# B212C.net
KiCad netlist of a schematic drawn in EAGLE
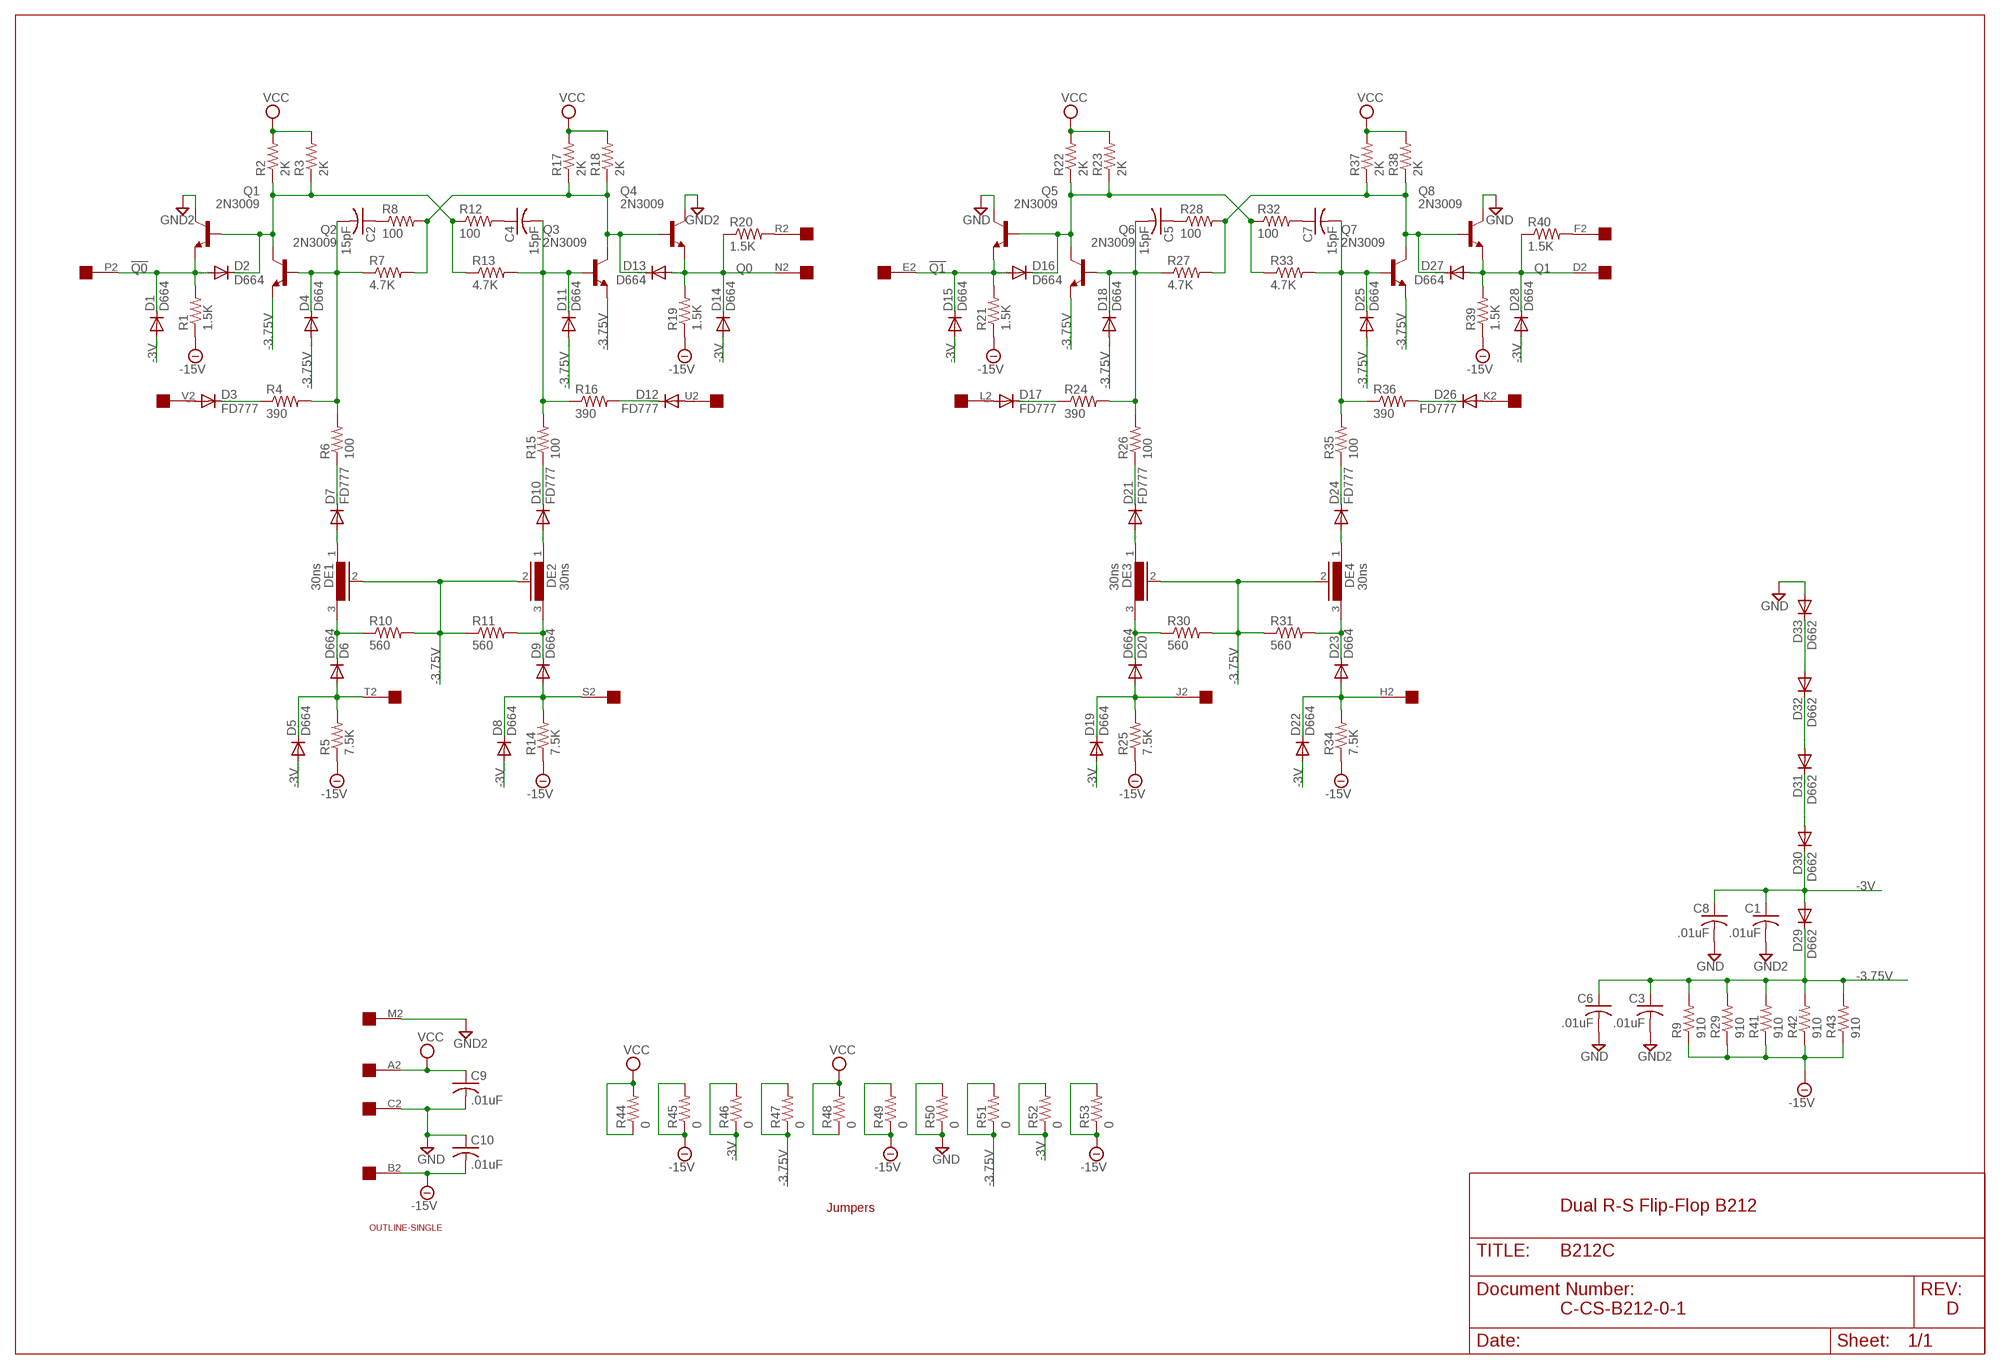
[diagram p0: schematic, sheet 1]

(export (version "E")
  (design (tool "Eeschema 10.0.6"))
  (components
    (comp (ref "C1")
      (value ".01uF")
      (footprint "eagle-import:C063-025X075")
      (libsource (lib "eagle-import") (part "C-US"))
    )
    (comp (ref "C2")
      (value "15pF")
      (footprint "eagle-import:C063-025X075")
      (libsource (lib "eagle-import") (part "C-US"))
    )
    (comp (ref "C3")
      (value ".01uF")
      (footprint "eagle-import:C063-025X075")
      (libsource (lib "eagle-import") (part "C-US"))
    )
    (comp (ref "C4")
      (value "15pF")
      (footprint "eagle-import:C050-025X075")
      (libsource (lib "eagle-import") (part "C-US050-025X075"))
    )
    (comp (ref "C5")
      (value "15pF")
      (footprint "eagle-import:C063-025X075")
      (libsource (lib "eagle-import") (part "C-US"))
    )
    (comp (ref "C6")
      (value ".01uF")
      (footprint "eagle-import:C063-025X075")
      (libsource (lib "eagle-import") (part "C-US"))
    )
    (comp (ref "C7")
      (value "15pF")
      (footprint "eagle-import:C063-025X075")
      (libsource (lib "eagle-import") (part "C-US"))
    )
    (comp (ref "C8")
      (value ".01uF")
      (footprint "eagle-import:C063-025X075")
      (libsource (lib "eagle-import") (part "C-US"))
    )
    (comp (ref "C9")
      (value ".01uF")
      (footprint "eagle-import:C063-025X075")
      (libsource (lib "eagle-import") (part "C-US"))
    )
    (comp (ref "C10")
      (value ".01uF")
      (footprint "eagle-import:C063-025X075")
      (libsource (lib "eagle-import") (part "C-US"))
    )
    (comp (ref "D1")
      (value "D664")
      (footprint "eagle-import:DO35-10")
      (libsource (lib "eagle-import") (part "DIODE-DO35-10"))
    )
    (comp (ref "D2")
      (value "D664")
      (footprint "eagle-import:DO35-10")
      (libsource (lib "eagle-import") (part "DIODE-DO35-10"))
    )
    (comp (ref "D3")
      (value "FD777")
      (footprint "eagle-import:DO35-10")
      (libsource (lib "eagle-import") (part "DIODE-DO35-10"))
    )
    (comp (ref "D4")
      (value "D664")
      (footprint "eagle-import:DO35-10")
      (libsource (lib "eagle-import") (part "DIODE-DO35-10"))
    )
    (comp (ref "D5")
      (value "D664")
      (footprint "eagle-import:DO35-10")
      (libsource (lib "eagle-import") (part "DIODE-DO35-10"))
    )
    (comp (ref "D6")
      (value "D664")
      (footprint "eagle-import:DO35-10")
      (libsource (lib "eagle-import") (part "DIODE-DO35-10"))
    )
    (comp (ref "D7")
      (value "FD777")
      (footprint "eagle-import:DO35-10")
      (libsource (lib "eagle-import") (part "DIODE-DO35-10"))
    )
    (comp (ref "D8")
      (value "D664")
      (footprint "eagle-import:DO35-10")
      (libsource (lib "eagle-import") (part "DIODE-DO35-10"))
    )
    (comp (ref "D9")
      (value "D664")
      (footprint "eagle-import:DO35-10")
      (libsource (lib "eagle-import") (part "DIODE-DO35-10"))
    )
    (comp (ref "D10")
      (value "FD777")
      (footprint "eagle-import:DO35-10")
      (libsource (lib "eagle-import") (part "DIODE-DO35-10"))
    )
    (comp (ref "D11")
      (value "D664")
      (footprint "eagle-import:DO35-10")
      (libsource (lib "eagle-import") (part "DIODE-DO35-10"))
    )
    (comp (ref "D12")
      (value "FD777")
      (footprint "eagle-import:DO35-10")
      (libsource (lib "eagle-import") (part "DIODE-DO35-10"))
    )
    (comp (ref "D13")
      (value "D664")
      (footprint "eagle-import:DO35-10")
      (libsource (lib "eagle-import") (part "DIODE-DO35-10"))
    )
    (comp (ref "D14")
      (value "D664")
      (footprint "eagle-import:DO35-10")
      (libsource (lib "eagle-import") (part "DIODE-DO35-10"))
    )
    (comp (ref "D15")
      (value "D664")
      (footprint "eagle-import:DO35-10")
      (libsource (lib "eagle-import") (part "DIODE-DO35-10"))
    )
    (comp (ref "D16")
      (value "D664")
      (footprint "eagle-import:DO35-10")
      (libsource (lib "eagle-import") (part "DIODE-DO35-10"))
    )
    (comp (ref "D17")
      (value "FD777")
      (footprint "eagle-import:DO35-10")
      (libsource (lib "eagle-import") (part "DIODE-DO35-10"))
    )
    (comp (ref "D18")
      (value "D664")
      (footprint "eagle-import:DO35-10")
      (libsource (lib "eagle-import") (part "DIODE-DO35-10"))
    )
    (comp (ref "D19")
      (value "D664")
      (footprint "eagle-import:DO35-10")
      (libsource (lib "eagle-import") (part "DIODE-DO35-10"))
    )
    (comp (ref "D20")
      (value "D664")
      (footprint "eagle-import:DO35-10")
      (libsource (lib "eagle-import") (part "DIODE-DO35-10"))
    )
    (comp (ref "D21")
      (value "FD777")
      (footprint "eagle-import:DO35-10")
      (libsource (lib "eagle-import") (part "DIODE-DO35-10"))
    )
    (comp (ref "D22")
      (value "D664")
      (footprint "eagle-import:DO35-10")
      (libsource (lib "eagle-import") (part "DIODE-DO35-10"))
    )
    (comp (ref "D23")
      (value "D664")
      (footprint "eagle-import:DO35-10")
      (libsource (lib "eagle-import") (part "DIODE-DO35-10"))
    )
    (comp (ref "D24")
      (value "FD777")
      (footprint "eagle-import:DO35-10")
      (libsource (lib "eagle-import") (part "DIODE-DO35-10"))
    )
    (comp (ref "D25")
      (value "D664")
      (footprint "eagle-import:DO35-10")
      (libsource (lib "eagle-import") (part "DIODE-DO35-10"))
    )
    (comp (ref "D26")
      (value "FD777")
      (footprint "eagle-import:DO35-10")
      (libsource (lib "eagle-import") (part "DIODE-DO35-10"))
    )
    (comp (ref "D27")
      (value "D664")
      (footprint "eagle-import:DO35-10")
      (libsource (lib "eagle-import") (part "DIODE-DO35-10"))
    )
    (comp (ref "D28")
      (value "D664")
      (footprint "eagle-import:DO35-10")
      (libsource (lib "eagle-import") (part "DIODE-DO35-10"))
    )
    (comp (ref "D29")
      (value "D662")
      (footprint "eagle-import:DO35-10")
      (libsource (lib "eagle-import") (part "DIODE-DO35-10"))
    )
    (comp (ref "D30")
      (value "D662")
      (footprint "eagle-import:DO35-10")
      (libsource (lib "eagle-import") (part "DIODE-DO35-10"))
    )
    (comp (ref "D31")
      (value "D662")
      (footprint "eagle-import:DO35-10")
      (libsource (lib "eagle-import") (part "DIODE-DO35-10"))
    )
    (comp (ref "D32")
      (value "D662")
      (footprint "eagle-import:DO35-10")
      (libsource (lib "eagle-import") (part "DIODE-DO35-10"))
    )
    (comp (ref "D33")
      (value "D662")
      (footprint "eagle-import:DO35-10")
      (libsource (lib "eagle-import") (part "DIODE-DO35-10"))
    )
    (comp (ref "DE1")
      (value "30ns")
      (footprint "eagle-import:RCL-L-00-05")
      (libsource (lib "eagle-import") (part "RCL-L-00-05"))
    )
    (comp (ref "DE2")
      (value "30ns")
      (footprint "eagle-import:RCL-L-00-05")
      (libsource (lib "eagle-import") (part "RCL-L-00-05"))
    )
    (comp (ref "DE3")
      (value "30ns")
      (footprint "eagle-import:RCL-L-00-05")
      (libsource (lib "eagle-import") (part "RCL-L-00-05"))
    )
    (comp (ref "DE4")
      (value "30ns")
      (footprint "eagle-import:RCL-L-00-05")
      (libsource (lib "eagle-import") (part "RCL-L-00-05"))
    )
    (comp (ref "Q1")
      (value "2N3009")
      (footprint "eagle-import:TO5")
      (libsource (lib "eagle-import") (part "-NPN-TO5"))
    )
    (comp (ref "Q2")
      (value "2N3009")
      (footprint "eagle-import:TO5")
      (libsource (lib "eagle-import") (part "-NPN-TO5"))
    )
    (comp (ref "Q3")
      (value "2N3009")
      (footprint "eagle-import:TO5")
      (libsource (lib "eagle-import") (part "-NPN-TO5"))
    )
    (comp (ref "Q4")
      (value "2N3009")
      (footprint "eagle-import:TO5")
      (libsource (lib "eagle-import") (part "-NPN-TO5"))
    )
    (comp (ref "Q5")
      (value "2N3009")
      (footprint "eagle-import:TO5")
      (libsource (lib "eagle-import") (part "-NPN-TO5"))
    )
    (comp (ref "Q6")
      (value "2N3009")
      (footprint "eagle-import:TO5")
      (libsource (lib "eagle-import") (part "-NPN-TO5"))
    )
    (comp (ref "Q7")
      (value "2N3009")
      (footprint "eagle-import:TO5")
      (libsource (lib "eagle-import") (part "-NPN-TO5"))
    )
    (comp (ref "Q8")
      (value "2N3009")
      (footprint "eagle-import:TO5")
      (libsource (lib "eagle-import") (part "-NPN-TO5"))
    )
    (comp (ref "R1")
      (value "1.5K")
      (footprint "eagle-import:0207_10")
      (libsource (lib "eagle-import") (part "R-US_0207/10"))
    )
    (comp (ref "R2")
      (value "2K")
      (footprint "eagle-import:0207_10")
      (libsource (lib "eagle-import") (part "R-US_0207/10"))
    )
    (comp (ref "R3")
      (value "2K")
      (footprint "eagle-import:0207_10")
      (libsource (lib "eagle-import") (part "R-US_0207/10"))
    )
    (comp (ref "R4")
      (value "390")
      (footprint "eagle-import:0207_10")
      (libsource (lib "eagle-import") (part "R-US_0207/10"))
    )
    (comp (ref "R5")
      (value "7.5K")
      (footprint "eagle-import:0207_10")
      (libsource (lib "eagle-import") (part "R-US_0207/10"))
    )
    (comp (ref "R6")
      (value "100")
      (footprint "eagle-import:0207_10")
      (libsource (lib "eagle-import") (part "R-US_0207/10"))
    )
    (comp (ref "R7")
      (value "4.7K")
      (footprint "eagle-import:0207_10")
      (libsource (lib "eagle-import") (part "R-US_0207/10"))
    )
    (comp (ref "R8")
      (value "100")
      (footprint "eagle-import:0207_10")
      (libsource (lib "eagle-import") (part "R-US_0207/10"))
    )
    (comp (ref "R9")
      (value "910")
      (footprint "eagle-import:0207_10")
      (libsource (lib "eagle-import") (part "R-US_0207/10"))
    )
    (comp (ref "R10")
      (value "560")
      (footprint "eagle-import:0207_10")
      (libsource (lib "eagle-import") (part "R-US_0207/10"))
    )
    (comp (ref "R11")
      (value "560")
      (footprint "eagle-import:0207_10")
      (libsource (lib "eagle-import") (part "R-US_0207/10"))
    )
    (comp (ref "R12")
      (value "100")
      (footprint "eagle-import:0207_10")
      (libsource (lib "eagle-import") (part "R-US_0207/10"))
    )
    (comp (ref "R13")
      (value "4.7K")
      (footprint "eagle-import:0207_10")
      (libsource (lib "eagle-import") (part "R-US_0207/10"))
    )
    (comp (ref "R14")
      (value "7.5K")
      (footprint "eagle-import:0207_10")
      (libsource (lib "eagle-import") (part "R-US_0207/10"))
    )
    (comp (ref "R15")
      (value "100")
      (footprint "eagle-import:0207_10")
      (libsource (lib "eagle-import") (part "R-US_0207/10"))
    )
    (comp (ref "R16")
      (value "390")
      (footprint "eagle-import:0207_10")
      (libsource (lib "eagle-import") (part "R-US_0207/10"))
    )
    (comp (ref "R17")
      (value "2K")
      (footprint "eagle-import:0207_10")
      (libsource (lib "eagle-import") (part "R-US_0207/10"))
    )
    (comp (ref "R18")
      (value "2K")
      (footprint "eagle-import:0207_10")
      (libsource (lib "eagle-import") (part "R-US_0207/10"))
    )
    (comp (ref "R19")
      (value "1.5K")
      (footprint "eagle-import:0207_10")
      (libsource (lib "eagle-import") (part "R-US_0207/10"))
    )
    (comp (ref "R20")
      (value "1.5K")
      (footprint "eagle-import:0207_10")
      (libsource (lib "eagle-import") (part "R-US_0207/10"))
    )
    (comp (ref "R21")
      (value "1.5K")
      (footprint "eagle-import:0207_10")
      (libsource (lib "eagle-import") (part "R-US_0207/10"))
    )
    (comp (ref "R22")
      (value "2K")
      (footprint "eagle-import:0207_10")
      (libsource (lib "eagle-import") (part "R-US_0207/10"))
    )
    (comp (ref "R23")
      (value "2K")
      (footprint "eagle-import:0207_10")
      (libsource (lib "eagle-import") (part "R-US_0207/10"))
    )
    (comp (ref "R24")
      (value "390")
      (footprint "eagle-import:0207_10")
      (libsource (lib "eagle-import") (part "R-US_0207/10"))
    )
    (comp (ref "R25")
      (value "7.5K")
      (footprint "eagle-import:0207_10")
      (libsource (lib "eagle-import") (part "R-US_0207/10"))
    )
    (comp (ref "R26")
      (value "100")
      (footprint "eagle-import:0207_10")
      (libsource (lib "eagle-import") (part "R-US_0207/10"))
    )
    (comp (ref "R27")
      (value "4.7K")
      (footprint "eagle-import:0207_10")
      (libsource (lib "eagle-import") (part "R-US_0207/10"))
    )
    (comp (ref "R28")
      (value "100")
      (footprint "eagle-import:0207_10")
      (libsource (lib "eagle-import") (part "R-US_0207/10"))
    )
    (comp (ref "R29")
      (value "910")
      (footprint "eagle-import:0207_10")
      (libsource (lib "eagle-import") (part "R-US_0207/10"))
    )
    (comp (ref "R30")
      (value "560")
      (footprint "eagle-import:0207_10")
      (libsource (lib "eagle-import") (part "R-US_0207/10"))
    )
    (comp (ref "R31")
      (value "560")
      (footprint "eagle-import:0207_10")
      (libsource (lib "eagle-import") (part "R-US_0207/10"))
    )
    (comp (ref "R32")
      (value "100")
      (footprint "eagle-import:0207_10")
      (libsource (lib "eagle-import") (part "R-US_0207/10"))
    )
    (comp (ref "R33")
      (value "4.7K")
      (footprint "eagle-import:0207_10")
      (libsource (lib "eagle-import") (part "R-US_0207/10"))
    )
    (comp (ref "R34")
      (value "7.5K")
      (footprint "eagle-import:0207_10")
      (libsource (lib "eagle-import") (part "R-US_0207/10"))
    )
    (comp (ref "R35")
      (value "100")
      (footprint "eagle-import:0207_10")
      (libsource (lib "eagle-import") (part "R-US_0207/10"))
    )
    (comp (ref "R36")
      (value "390")
      (footprint "eagle-import:0207_10")
      (libsource (lib "eagle-import") (part "R-US_0207/10"))
    )
    (comp (ref "R37")
      (value "2K")
      (footprint "eagle-import:0207_10")
      (libsource (lib "eagle-import") (part "R-US_0207/10"))
    )
    (comp (ref "R38")
      (value "2K")
      (footprint "eagle-import:0207_10")
      (libsource (lib "eagle-import") (part "R-US_0207/10"))
    )
    (comp (ref "R39")
      (value "1.5K")
      (footprint "eagle-import:0207_10")
      (libsource (lib "eagle-import") (part "R-US_0207/10"))
    )
    (comp (ref "R40")
      (value "1.5K")
      (footprint "eagle-import:0207_10")
      (libsource (lib "eagle-import") (part "R-US_0207/10"))
    )
    (comp (ref "R41")
      (value "910")
      (footprint "eagle-import:0207_10")
      (libsource (lib "eagle-import") (part "R-US_0207/10"))
    )
    (comp (ref "R42")
      (value "910")
      (footprint "eagle-import:0207_10")
      (libsource (lib "eagle-import") (part "R-US_0207/10"))
    )
    (comp (ref "R43")
      (value "910")
      (footprint "eagle-import:0207_10")
      (libsource (lib "eagle-import") (part "R-US_0207/10"))
    )
    (comp (ref "R44")
      (value "0")
      (footprint "eagle-import:0207_10")
      (libsource (lib "eagle-import") (part "R-US_0207/10"))
    )
    (comp (ref "R45")
      (value "0")
      (footprint "eagle-import:0207_10")
      (libsource (lib "eagle-import") (part "R-US_0207/10"))
    )
    (comp (ref "R46")
      (value "0")
      (footprint "eagle-import:0207_10")
      (libsource (lib "eagle-import") (part "R-US_0207/10"))
    )
    (comp (ref "R47")
      (value "0")
      (footprint "eagle-import:0207_10")
      (libsource (lib "eagle-import") (part "R-US_0207/10"))
    )
    (comp (ref "R48")
      (value "0")
      (footprint "eagle-import:0207_10")
      (libsource (lib "eagle-import") (part "R-US_0207/10"))
    )
    (comp (ref "R49")
      (value "0")
      (footprint "eagle-import:0207_10")
      (libsource (lib "eagle-import") (part "R-US_0207/10"))
    )
    (comp (ref "R50")
      (value "0")
      (footprint "eagle-import:0207_10")
      (libsource (lib "eagle-import") (part "R-US_0207/10"))
    )
    (comp (ref "R51")
      (value "0")
      (footprint "eagle-import:0207_10")
      (libsource (lib "eagle-import") (part "R-US_0207/10"))
    )
    (comp (ref "R52")
      (value "0")
      (footprint "eagle-import:0207_10")
      (libsource (lib "eagle-import") (part "R-US_0207/10"))
    )
    (comp (ref "R53")
      (value "0")
      (footprint "eagle-import:0207_10")
      (libsource (lib "eagle-import") (part "R-US_0207/10"))
    )
    (comp (ref "U$1")
      (value "OUTLINE-SINGLE")
      (footprint "eagle-import:SINGLE")
      (libsource (lib "eagle-import") (part "OUTLINE-SINGLE"))
    )
    (comp (ref "U$2")
      (value "EDGE-1")
      (footprint "eagle-import:EDGE-CON1")
      (libsource (lib "eagle-import") (part "EDGE-1"))
    )
  )
  (nets
    (net (code "1") (name "-15V") (class "Default")
      (node (ref "C10") (pin "2") (pinfunction "2_2") (pintype "passive"))
      (node (ref "R1") (pin "1") (pinfunction "1_1") (pintype "passive"))
      (node (ref "R14") (pin "1") (pinfunction "1_1") (pintype "passive"))
      (node (ref "R19") (pin "1") (pinfunction "1_1") (pintype "passive"))
      (node (ref "R21") (pin "1") (pinfunction "1_1") (pintype "passive"))
      (node (ref "R25") (pin "1") (pinfunction "1_1") (pintype "passive"))
      (node (ref "R29") (pin "1") (pinfunction "1_1") (pintype "passive"))
      (node (ref "R34") (pin "1") (pinfunction "1_1") (pintype "passive"))
      (node (ref "R39") (pin "1") (pinfunction "1_1") (pintype "passive"))
      (node (ref "R41") (pin "1") (pinfunction "1_1") (pintype "passive"))
      (node (ref "R42") (pin "1") (pinfunction "1_1") (pintype "passive"))
      (node (ref "R43") (pin "1") (pinfunction "1_1") (pintype "passive"))
      (node (ref "R45") (pin "1") (pinfunction "1_1") (pintype "passive"))
      (node (ref "R45") (pin "2") (pinfunction "2_2") (pintype "passive"))
      (node (ref "R49") (pin "1") (pinfunction "1_1") (pintype "passive"))
      (node (ref "R49") (pin "2") (pinfunction "2_2") (pintype "passive"))
      (node (ref "R5") (pin "1") (pinfunction "1_1") (pintype "passive"))
      (node (ref "R53") (pin "1") (pinfunction "1_1") (pintype "passive"))
      (node (ref "R53") (pin "2") (pinfunction "2_2") (pintype "passive"))
      (node (ref "R9") (pin "1") (pinfunction "1_1") (pintype "passive"))
      (node (ref "U$2") (pin "B2") (pinfunction "1_B2") (pintype "bidirectional"))
    )
    (net (code "2") (name "/-3.75V") (class "Default")
      (node (ref "C3") (pin "1") (pinfunction "1_1") (pintype "passive"))
      (node (ref "C6") (pin "1") (pinfunction "1_1") (pintype "passive"))
      (node (ref "D11") (pin "A") (pinfunction "A_A") (pintype "passive"))
      (node (ref "D18") (pin "A") (pinfunction "A_A") (pintype "passive"))
      (node (ref "D25") (pin "A") (pinfunction "A_A") (pintype "passive"))
      (node (ref "D29") (pin "C") (pinfunction "C_C") (pintype "passive"))
      (node (ref "D4") (pin "A") (pinfunction "A_A") (pintype "passive"))
      (node (ref "DE1") (pin "2") (pinfunction "2_2") (pintype "passive"))
      (node (ref "DE2") (pin "2") (pinfunction "2_2") (pintype "passive"))
      (node (ref "DE3") (pin "2") (pinfunction "2_2") (pintype "passive"))
      (node (ref "DE4") (pin "2") (pinfunction "2_2") (pintype "passive"))
      (node (ref "Q2") (pin "1") (pinfunction "E_1") (pintype "passive"))
      (node (ref "Q3") (pin "1") (pinfunction "E_1") (pintype "passive"))
      (node (ref "Q6") (pin "1") (pinfunction "E_1") (pintype "passive"))
      (node (ref "Q7") (pin "1") (pinfunction "E_1") (pintype "passive"))
      (node (ref "R10") (pin "2") (pinfunction "2_2") (pintype "passive"))
      (node (ref "R11") (pin "1") (pinfunction "1_1") (pintype "passive"))
      (node (ref "R29") (pin "2") (pinfunction "2_2") (pintype "passive"))
      (node (ref "R30") (pin "2") (pinfunction "2_2") (pintype "passive"))
      (node (ref "R31") (pin "1") (pinfunction "1_1") (pintype "passive"))
      (node (ref "R41") (pin "2") (pinfunction "2_2") (pintype "passive"))
      (node (ref "R42") (pin "2") (pinfunction "2_2") (pintype "passive"))
      (node (ref "R43") (pin "2") (pinfunction "2_2") (pintype "passive"))
      (node (ref "R47") (pin "1") (pinfunction "1_1") (pintype "passive"))
      (node (ref "R47") (pin "2") (pinfunction "2_2") (pintype "passive"))
      (node (ref "R51") (pin "1") (pinfunction "1_1") (pintype "passive"))
      (node (ref "R51") (pin "2") (pinfunction "2_2") (pintype "passive"))
      (node (ref "R9") (pin "2") (pinfunction "2_2") (pintype "passive"))
    )
    (net (code "3") (name "/-3V") (class "Default")
      (node (ref "C1") (pin "1") (pinfunction "1_1") (pintype "passive"))
      (node (ref "C8") (pin "1") (pinfunction "1_1") (pintype "passive"))
      (node (ref "D1") (pin "A") (pinfunction "A_A") (pintype "passive"))
      (node (ref "D14") (pin "A") (pinfunction "A_A") (pintype "passive"))
      (node (ref "D15") (pin "A") (pinfunction "A_A") (pintype "passive"))
      (node (ref "D19") (pin "A") (pinfunction "A_A") (pintype "passive"))
      (node (ref "D22") (pin "A") (pinfunction "A_A") (pintype "passive"))
      (node (ref "D28") (pin "A") (pinfunction "A_A") (pintype "passive"))
      (node (ref "D29") (pin "A") (pinfunction "A_A") (pintype "passive"))
      (node (ref "D30") (pin "C") (pinfunction "C_C") (pintype "passive"))
      (node (ref "D5") (pin "A") (pinfunction "A_A") (pintype "passive"))
      (node (ref "D8") (pin "A") (pinfunction "A_A") (pintype "passive"))
      (node (ref "R46") (pin "1") (pinfunction "1_1") (pintype "passive"))
      (node (ref "R46") (pin "2") (pinfunction "2_2") (pintype "passive"))
      (node (ref "R52") (pin "1") (pinfunction "1_1") (pintype "passive"))
      (node (ref "R52") (pin "2") (pinfunction "2_2") (pintype "passive"))
    )
    (net (code "4") (name "/Q0") (class "Default")
      (node (ref "D13") (pin "A") (pinfunction "A_A") (pintype "passive"))
      (node (ref "D14") (pin "C") (pinfunction "C_C") (pintype "passive"))
      (node (ref "Q4") (pin "1") (pinfunction "E_1") (pintype "passive"))
      (node (ref "R19") (pin "2") (pinfunction "2_2") (pintype "passive"))
      (node (ref "R20") (pin "1") (pinfunction "1_1") (pintype "passive"))
      (node (ref "U$2") (pin "N2") (pinfunction "1_N2") (pintype "bidirectional"))
    )
    (net (code "5") (name "/Q1") (class "Default")
      (node (ref "D27") (pin "A") (pinfunction "A_A") (pintype "passive"))
      (node (ref "D28") (pin "C") (pinfunction "C_C") (pintype "passive"))
      (node (ref "Q8") (pin "1") (pinfunction "E_1") (pintype "passive"))
      (node (ref "R39") (pin "2") (pinfunction "2_2") (pintype "passive"))
      (node (ref "R40") (pin "1") (pinfunction "1_1") (pintype "passive"))
      (node (ref "U$2") (pin "D2") (pinfunction "1_D2") (pintype "bidirectional"))
    )
    (net (code "6") (name "/~{Q0}") (class "Default")
      (node (ref "D1") (pin "C") (pinfunction "C_C") (pintype "passive"))
      (node (ref "D2") (pin "A") (pinfunction "A_A") (pintype "passive"))
      (node (ref "Q1") (pin "1") (pinfunction "E_1") (pintype "passive"))
      (node (ref "R1") (pin "2") (pinfunction "2_2") (pintype "passive"))
      (node (ref "U$2") (pin "P2") (pinfunction "1_P2") (pintype "bidirectional"))
    )
    (net (code "7") (name "/~{Q1}") (class "Default")
      (node (ref "D15") (pin "C") (pinfunction "C_C") (pintype "passive"))
      (node (ref "D16") (pin "A") (pinfunction "A_A") (pintype "passive"))
      (node (ref "Q5") (pin "1") (pinfunction "E_1") (pintype "passive"))
      (node (ref "R21") (pin "2") (pinfunction "2_2") (pintype "passive"))
      (node (ref "U$2") (pin "E2") (pinfunction "1_E2") (pintype "bidirectional"))
    )
    (net (code "8") (name "GND") (class "Default")
      (node (ref "C10") (pin "1") (pinfunction "1_1") (pintype "passive"))
      (node (ref "C6") (pin "2") (pinfunction "2_2") (pintype "passive"))
      (node (ref "C8") (pin "2") (pinfunction "2_2") (pintype "passive"))
      (node (ref "C9") (pin "2") (pinfunction "2_2") (pintype "passive"))
      (node (ref "D33") (pin "A") (pinfunction "A_A") (pintype "passive"))
      (node (ref "Q5") (pin "3") (pinfunction "C_3") (pintype "passive"))
      (node (ref "Q8") (pin "3") (pinfunction "C_3") (pintype "passive"))
      (node (ref "R50") (pin "1") (pinfunction "1_1") (pintype "passive"))
      (node (ref "R50") (pin "2") (pinfunction "2_2") (pintype "passive"))
      (node (ref "U$2") (pin "C2") (pinfunction "1_C2") (pintype "bidirectional"))
    )
    (net (code "9") (name "GND2") (class "Default")
      (node (ref "C1") (pin "2") (pinfunction "2_2") (pintype "passive"))
      (node (ref "C3") (pin "2") (pinfunction "2_2") (pintype "passive"))
      (node (ref "Q1") (pin "3") (pinfunction "C_3") (pintype "passive"))
      (node (ref "Q4") (pin "3") (pinfunction "C_3") (pintype "passive"))
      (node (ref "U$2") (pin "M2") (pinfunction "1_M2") (pintype "bidirectional"))
    )
    (net (code "10") (name "Net-(C2-Pad1)") (class "Default")
      (node (ref "C2") (pin "1") (pinfunction "1_1") (pintype "passive"))
      (node (ref "R8") (pin "1") (pinfunction "1_1") (pintype "passive"))
    )
    (net (code "11") (name "Net-(C4-Pad1)") (class "Default")
      (node (ref "C4") (pin "1") (pinfunction "1_1") (pintype "passive"))
      (node (ref "R12") (pin "2") (pinfunction "2_2") (pintype "passive"))
    )
    (net (code "12") (name "Net-(C5-Pad1)") (class "Default")
      (node (ref "C5") (pin "1") (pinfunction "1_1") (pintype "passive"))
      (node (ref "R28") (pin "1") (pinfunction "1_1") (pintype "passive"))
    )
    (net (code "13") (name "Net-(C7-Pad1)") (class "Default")
      (node (ref "C7") (pin "1") (pinfunction "1_1") (pintype "passive"))
      (node (ref "R32") (pin "2") (pinfunction "2_2") (pintype "passive"))
    )
    (net (code "14") (name "Net-(D3-PadC)") (class "Default")
      (node (ref "D3") (pin "C") (pinfunction "C_C") (pintype "passive"))
      (node (ref "R4") (pin "1") (pinfunction "1_1") (pintype "passive"))
    )
    (net (code "15") (name "Net-(D6-PadC)") (class "Default")
      (node (ref "D6") (pin "C") (pinfunction "C_C") (pintype "passive"))
      (node (ref "DE1") (pin "3") (pinfunction "3_3") (pintype "passive"))
      (node (ref "R10") (pin "1") (pinfunction "1_1") (pintype "passive"))
    )
    (net (code "16") (name "Net-(D7-PadA)") (class "Default")
      (node (ref "D7") (pin "A") (pinfunction "A_A") (pintype "passive"))
      (node (ref "DE1") (pin "1") (pinfunction "1_1") (pintype "passive"))
    )
    (net (code "17") (name "Net-(D7-PadC)") (class "Default")
      (node (ref "D7") (pin "C") (pinfunction "C_C") (pintype "passive"))
      (node (ref "R6") (pin "1") (pinfunction "1_1") (pintype "passive"))
    )
    (net (code "18") (name "Net-(D9-PadC)") (class "Default")
      (node (ref "D9") (pin "C") (pinfunction "C_C") (pintype "passive"))
      (node (ref "DE2") (pin "3") (pinfunction "3_3") (pintype "passive"))
      (node (ref "R11") (pin "2") (pinfunction "2_2") (pintype "passive"))
    )
    (net (code "19") (name "Net-(D10-PadA)") (class "Default")
      (node (ref "D10") (pin "A") (pinfunction "A_A") (pintype "passive"))
      (node (ref "DE2") (pin "1") (pinfunction "1_1") (pintype "passive"))
    )
    (net (code "20") (name "Net-(D10-PadC)") (class "Default")
      (node (ref "D10") (pin "C") (pinfunction "C_C") (pintype "passive"))
      (node (ref "R15") (pin "1") (pinfunction "1_1") (pintype "passive"))
    )
    (net (code "21") (name "Net-(D12-PadC)") (class "Default")
      (node (ref "D12") (pin "C") (pinfunction "C_C") (pintype "passive"))
      (node (ref "R16") (pin "2") (pinfunction "2_2") (pintype "passive"))
    )
    (net (code "22") (name "Net-(D17-PadC)") (class "Default")
      (node (ref "D17") (pin "C") (pinfunction "C_C") (pintype "passive"))
      (node (ref "R24") (pin "1") (pinfunction "1_1") (pintype "passive"))
    )
    (net (code "23") (name "Net-(D20-PadC)") (class "Default")
      (node (ref "D20") (pin "C") (pinfunction "C_C") (pintype "passive"))
      (node (ref "DE3") (pin "3") (pinfunction "3_3") (pintype "passive"))
      (node (ref "R30") (pin "1") (pinfunction "1_1") (pintype "passive"))
    )
    (net (code "24") (name "Net-(D21-PadA)") (class "Default")
      (node (ref "D21") (pin "A") (pinfunction "A_A") (pintype "passive"))
      (node (ref "DE3") (pin "1") (pinfunction "1_1") (pintype "passive"))
    )
    (net (code "25") (name "Net-(D21-PadC)") (class "Default")
      (node (ref "D21") (pin "C") (pinfunction "C_C") (pintype "passive"))
      (node (ref "R26") (pin "1") (pinfunction "1_1") (pintype "passive"))
    )
    (net (code "26") (name "Net-(D23-PadC)") (class "Default")
      (node (ref "D23") (pin "C") (pinfunction "C_C") (pintype "passive"))
      (node (ref "DE4") (pin "3") (pinfunction "3_3") (pintype "passive"))
      (node (ref "R31") (pin "2") (pinfunction "2_2") (pintype "passive"))
    )
    (net (code "27") (name "Net-(D24-PadA)") (class "Default")
      (node (ref "D24") (pin "A") (pinfunction "A_A") (pintype "passive"))
      (node (ref "DE4") (pin "1") (pinfunction "1_1") (pintype "passive"))
    )
    (net (code "28") (name "Net-(D24-PadC)") (class "Default")
      (node (ref "D24") (pin "C") (pinfunction "C_C") (pintype "passive"))
      (node (ref "R35") (pin "1") (pinfunction "1_1") (pintype "passive"))
    )
    (net (code "29") (name "Net-(D26-PadC)") (class "Default")
      (node (ref "D26") (pin "C") (pinfunction "C_C") (pintype "passive"))
      (node (ref "R36") (pin "2") (pinfunction "2_2") (pintype "passive"))
    )
    (net (code "30") (name "Net-(D30-PadA)") (class "Default")
      (node (ref "D30") (pin "A") (pinfunction "A_A") (pintype "passive"))
      (node (ref "D31") (pin "C") (pinfunction "C_C") (pintype "passive"))
    )
    (net (code "31") (name "Net-(D31-PadA)") (class "Default")
      (node (ref "D31") (pin "A") (pinfunction "A_A") (pintype "passive"))
      (node (ref "D32") (pin "C") (pinfunction "C_C") (pintype "passive"))
    )
    (net (code "32") (name "Net-(D32-PadA)") (class "Default")
      (node (ref "D32") (pin "A") (pinfunction "A_A") (pintype "passive"))
      (node (ref "D33") (pin "C") (pinfunction "C_C") (pintype "passive"))
    )
    (net (code "33") (name "Net-(Q1-B)") (class "Default")
      (node (ref "D2") (pin "C") (pinfunction "C_C") (pintype "passive"))
      (node (ref "Q1") (pin "2") (pinfunction "B_2") (pintype "passive"))
      (node (ref "Q2") (pin "3") (pinfunction "C_3") (pintype "passive"))
      (node (ref "R12") (pin "1") (pinfunction "1_1") (pintype "passive"))
      (node (ref "R13") (pin "1") (pinfunction "1_1") (pintype "passive"))
      (node (ref "R2") (pin "1") (pinfunction "1_1") (pintype "passive"))
      (node (ref "R3") (pin "1") (pinfunction "1_1") (pintype "passive"))
    )
    (net (code "34") (name "Net-(Q2-B)") (class "Default")
      (node (ref "C2") (pin "2") (pinfunction "2_2") (pintype "passive"))
      (node (ref "D4") (pin "C") (pinfunction "C_C") (pintype "passive"))
      (node (ref "Q2") (pin "2") (pinfunction "B_2") (pintype "passive"))
      (node (ref "R4") (pin "2") (pinfunction "2_2") (pintype "passive"))
      (node (ref "R6") (pin "2") (pinfunction "2_2") (pintype "passive"))
      (node (ref "R7") (pin "1") (pinfunction "1_1") (pintype "passive"))
    )
    (net (code "35") (name "Net-(Q3-B)") (class "Default")
      (node (ref "C4") (pin "2") (pinfunction "2_2") (pintype "passive"))
      (node (ref "D11") (pin "C") (pinfunction "C_C") (pintype "passive"))
      (node (ref "Q3") (pin "2") (pinfunction "B_2") (pintype "passive"))
      (node (ref "R13") (pin "2") (pinfunction "2_2") (pintype "passive"))
      (node (ref "R15") (pin "2") (pinfunction "2_2") (pintype "passive"))
      (node (ref "R16") (pin "1") (pinfunction "1_1") (pintype "passive"))
    )
    (net (code "36") (name "Net-(Q3-C)") (class "Default")
      (node (ref "D13") (pin "C") (pinfunction "C_C") (pintype "passive"))
      (node (ref "Q3") (pin "3") (pinfunction "C_3") (pintype "passive"))
      (node (ref "Q4") (pin "2") (pinfunction "B_2") (pintype "passive"))
      (node (ref "R17") (pin "1") (pinfunction "1_1") (pintype "passive"))
      (node (ref "R18") (pin "1") (pinfunction "1_1") (pintype "passive"))
      (node (ref "R7") (pin "2") (pinfunction "2_2") (pintype "passive"))
      (node (ref "R8") (pin "2") (pinfunction "2_2") (pintype "passive"))
    )
    (net (code "37") (name "Net-(Q5-B)") (class "Default")
      (node (ref "D16") (pin "C") (pinfunction "C_C") (pintype "passive"))
      (node (ref "Q5") (pin "2") (pinfunction "B_2") (pintype "passive"))
      (node (ref "Q6") (pin "3") (pinfunction "C_3") (pintype "passive"))
      (node (ref "R22") (pin "1") (pinfunction "1_1") (pintype "passive"))
      (node (ref "R23") (pin "1") (pinfunction "1_1") (pintype "passive"))
      (node (ref "R32") (pin "1") (pinfunction "1_1") (pintype "passive"))
      (node (ref "R33") (pin "1") (pinfunction "1_1") (pintype "passive"))
    )
    (net (code "38") (name "Net-(Q6-B)") (class "Default")
      (node (ref "C5") (pin "2") (pinfunction "2_2") (pintype "passive"))
      (node (ref "D18") (pin "C") (pinfunction "C_C") (pintype "passive"))
      (node (ref "Q6") (pin "2") (pinfunction "B_2") (pintype "passive"))
      (node (ref "R24") (pin "2") (pinfunction "2_2") (pintype "passive"))
      (node (ref "R26") (pin "2") (pinfunction "2_2") (pintype "passive"))
      (node (ref "R27") (pin "1") (pinfunction "1_1") (pintype "passive"))
    )
    (net (code "39") (name "Net-(Q7-B)") (class "Default")
      (node (ref "C7") (pin "2") (pinfunction "2_2") (pintype "passive"))
      (node (ref "D25") (pin "C") (pinfunction "C_C") (pintype "passive"))
      (node (ref "Q7") (pin "2") (pinfunction "B_2") (pintype "passive"))
      (node (ref "R33") (pin "2") (pinfunction "2_2") (pintype "passive"))
      (node (ref "R35") (pin "2") (pinfunction "2_2") (pintype "passive"))
      (node (ref "R36") (pin "1") (pinfunction "1_1") (pintype "passive"))
    )
    (net (code "40") (name "Net-(Q7-C)") (class "Default")
      (node (ref "D27") (pin "C") (pinfunction "C_C") (pintype "passive"))
      (node (ref "Q7") (pin "3") (pinfunction "C_3") (pintype "passive"))
      (node (ref "Q8") (pin "2") (pinfunction "B_2") (pintype "passive"))
      (node (ref "R27") (pin "2") (pinfunction "2_2") (pintype "passive"))
      (node (ref "R28") (pin "2") (pinfunction "2_2") (pintype "passive"))
      (node (ref "R37") (pin "1") (pinfunction "1_1") (pintype "passive"))
      (node (ref "R38") (pin "1") (pinfunction "1_1") (pintype "passive"))
    )
    (net (code "41") (name "Net-(U$2F-1)") (class "Default")
      (node (ref "R40") (pin "2") (pinfunction "2_2") (pintype "passive"))
      (node (ref "U$2") (pin "F2") (pinfunction "1_F2") (pintype "bidirectional"))
    )
    (net (code "42") (name "Net-(U$2G-1)") (class "Default")
      (node (ref "D22") (pin "C") (pinfunction "C_C") (pintype "passive"))
      (node (ref "D23") (pin "A") (pinfunction "A_A") (pintype "passive"))
      (node (ref "R34") (pin "2") (pinfunction "2_2") (pintype "passive"))
      (node (ref "U$2") (pin "H2") (pinfunction "1_H2") (pintype "bidirectional"))
    )
    (net (code "43") (name "Net-(U$2H-1)") (class "Default")
      (node (ref "D19") (pin "C") (pinfunction "C_C") (pintype "passive"))
      (node (ref "D20") (pin "A") (pinfunction "A_A") (pintype "passive"))
      (node (ref "R25") (pin "2") (pinfunction "2_2") (pintype "passive"))
      (node (ref "U$2") (pin "J2") (pinfunction "1_J2") (pintype "bidirectional"))
    )
    (net (code "44") (name "Net-(U$2I-1)") (class "Default")
      (node (ref "D26") (pin "A") (pinfunction "A_A") (pintype "passive"))
      (node (ref "U$2") (pin "K2") (pinfunction "1_K2") (pintype "bidirectional"))
    )
    (net (code "45") (name "Net-(U$2J-1)") (class "Default")
      (node (ref "D17") (pin "A") (pinfunction "A_A") (pintype "passive"))
      (node (ref "U$2") (pin "L2") (pinfunction "1_L2") (pintype "bidirectional"))
    )
    (net (code "46") (name "Net-(U$2N-1)") (class "Default")
      (node (ref "R20") (pin "2") (pinfunction "2_2") (pintype "passive"))
      (node (ref "U$2") (pin "R2") (pinfunction "1_R2") (pintype "bidirectional"))
    )
    (net (code "47") (name "Net-(U$2O-1)") (class "Default")
      (node (ref "D8") (pin "C") (pinfunction "C_C") (pintype "passive"))
      (node (ref "D9") (pin "A") (pinfunction "A_A") (pintype "passive"))
      (node (ref "R14") (pin "2") (pinfunction "2_2") (pintype "passive"))
      (node (ref "U$2") (pin "S2") (pinfunction "1_S2") (pintype "bidirectional"))
    )
    (net (code "48") (name "Net-(U$2P-1)") (class "Default")
      (node (ref "D5") (pin "C") (pinfunction "C_C") (pintype "passive"))
      (node (ref "D6") (pin "A") (pinfunction "A_A") (pintype "passive"))
      (node (ref "R5") (pin "2") (pinfunction "2_2") (pintype "passive"))
      (node (ref "U$2") (pin "T2") (pinfunction "1_T2") (pintype "bidirectional"))
    )
    (net (code "49") (name "Net-(U$2Q-1)") (class "Default")
      (node (ref "D12") (pin "A") (pinfunction "A_A") (pintype "passive"))
      (node (ref "U$2") (pin "U2") (pinfunction "1_U2") (pintype "bidirectional"))
    )
    (net (code "50") (name "Net-(U$2R-1)") (class "Default")
      (node (ref "D3") (pin "A") (pinfunction "A_A") (pintype "passive"))
      (node (ref "U$2") (pin "V2") (pinfunction "1_V2") (pintype "bidirectional"))
    )
    (net (code "51") (name "VCC") (class "Default")
      (node (ref "C9") (pin "1") (pinfunction "1_1") (pintype "passive"))
      (node (ref "R17") (pin "2") (pinfunction "2_2") (pintype "passive"))
      (node (ref "R18") (pin "2") (pinfunction "2_2") (pintype "passive"))
      (node (ref "R2") (pin "2") (pinfunction "2_2") (pintype "passive"))
      (node (ref "R22") (pin "2") (pinfunction "2_2") (pintype "passive"))
      (node (ref "R23") (pin "2") (pinfunction "2_2") (pintype "passive"))
      (node (ref "R3") (pin "2") (pinfunction "2_2") (pintype "passive"))
      (node (ref "R37") (pin "2") (pinfunction "2_2") (pintype "passive"))
      (node (ref "R38") (pin "2") (pinfunction "2_2") (pintype "passive"))
      (node (ref "R44") (pin "1") (pinfunction "1_1") (pintype "passive"))
      (node (ref "R44") (pin "2") (pinfunction "2_2") (pintype "passive"))
      (node (ref "R48") (pin "1") (pinfunction "1_1") (pintype "passive"))
      (node (ref "R48") (pin "2") (pinfunction "2_2") (pintype "passive"))
      (node (ref "U$2") (pin "A2") (pinfunction "1_A2") (pintype "bidirectional"))
    )
  )
)
